# MEGA_Shield.net
KiCad netlist of a schematic drawn in EAGLE
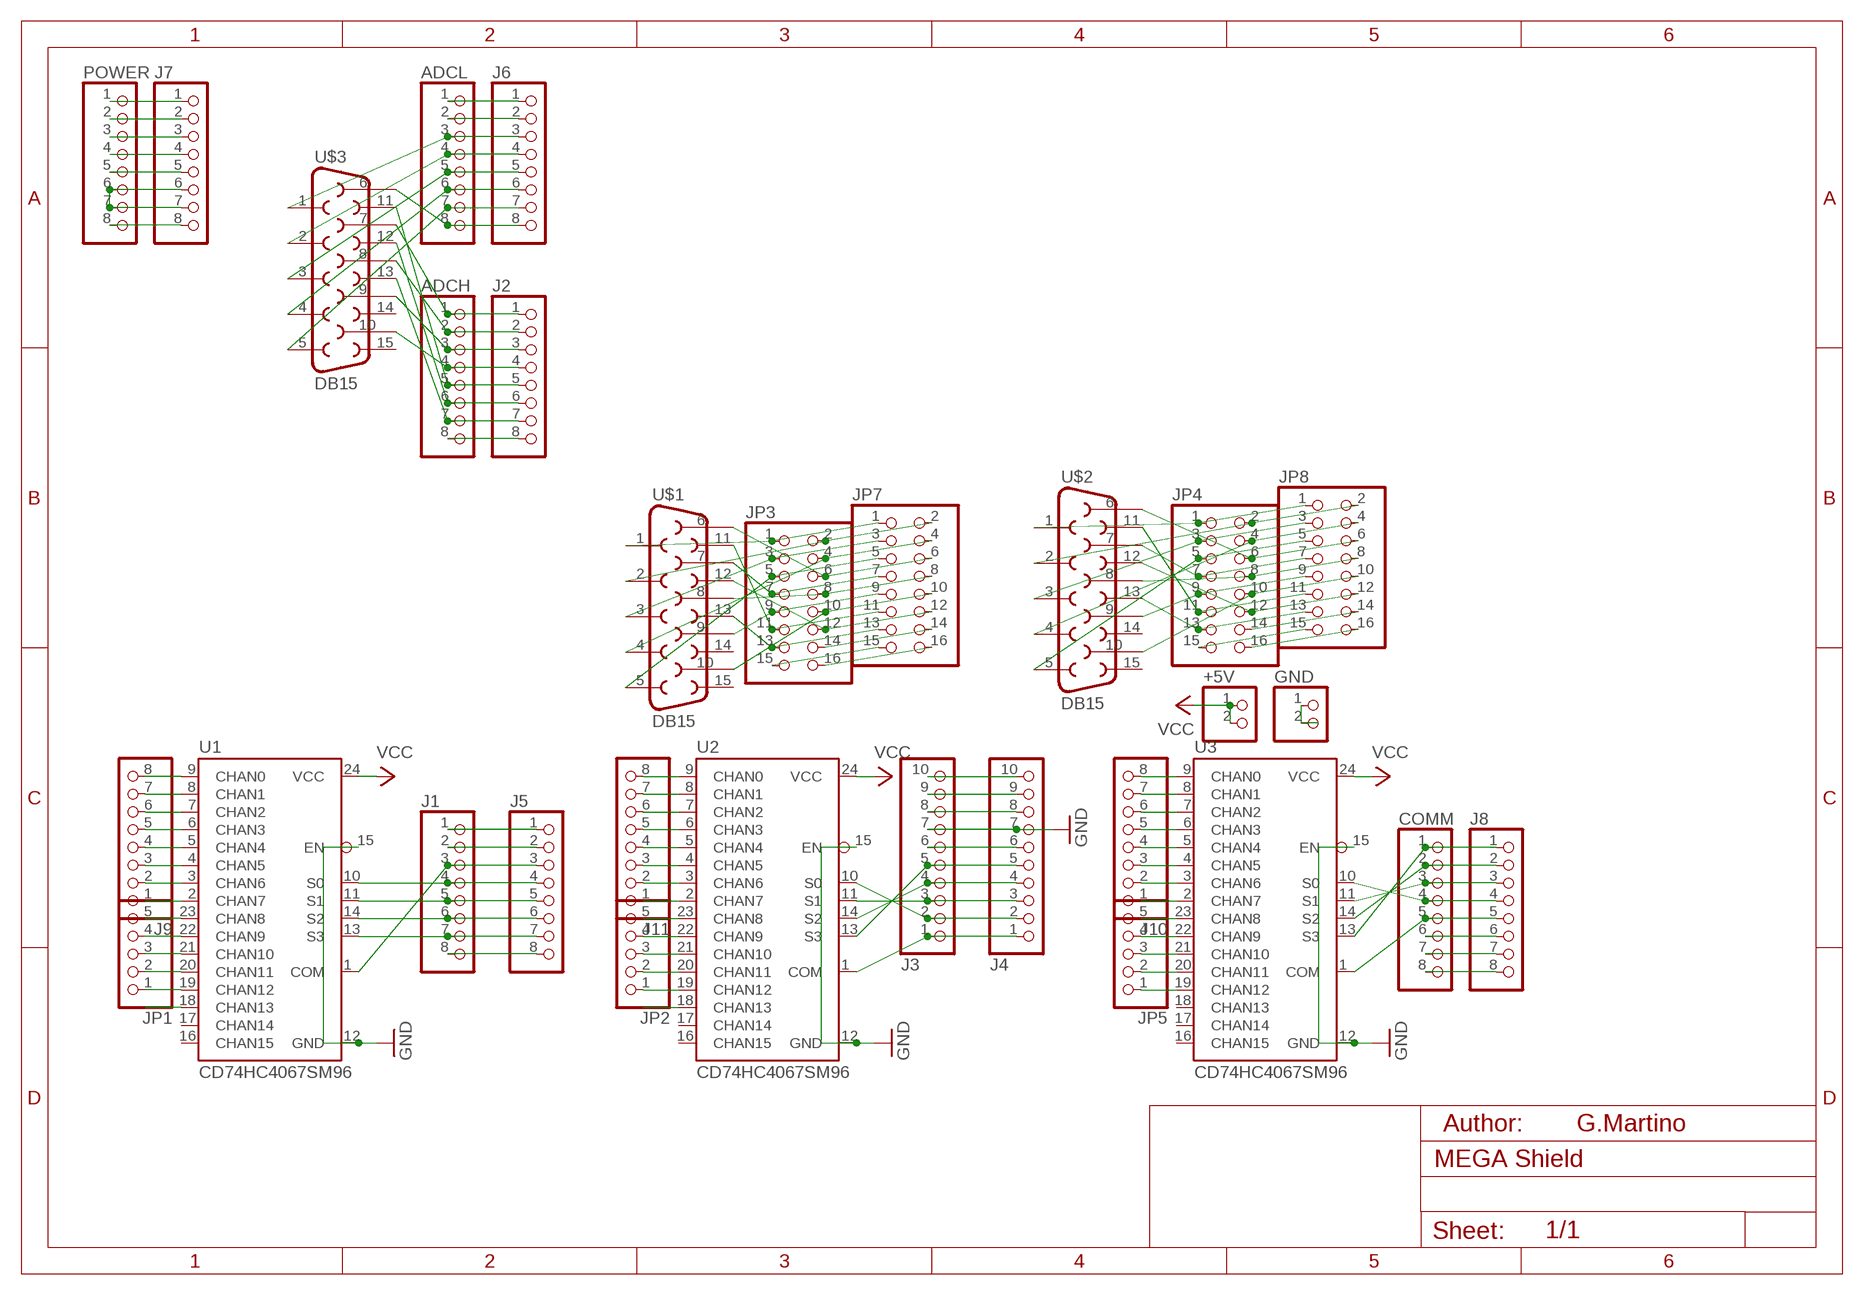
[diagram p0: schematic, sheet 1]

(export (version "E")
  (design (tool "Eeschema 10.0.6"))
  (components
    (comp (ref "+5V")
      (value "PINHD-1X2")
      (footprint "eagle-import:1X02")
      (libsource (lib "eagle-import") (part "PINHD-1X2"))
    )
    (comp (ref "ADCH")
      (value "PINHD-1X8TH")
      (footprint "eagle-import:1X08-TH")
      (libsource (lib "eagle-import") (part "PINHD-1X8TH"))
    )
    (comp (ref "ADCL")
      (value "PINHD-1X8TH")
      (footprint "eagle-import:1X08-TH")
      (libsource (lib "eagle-import") (part "PINHD-1X8TH"))
    )
    (comp (ref "COMM")
      (value "PINHD-1X8TH")
      (footprint "eagle-import:1X08-TH")
      (libsource (lib "eagle-import") (part "PINHD-1X8TH"))
    )
    (comp (ref "GND")
      (value "PINHD-1X2")
      (footprint "eagle-import:1X02")
      (libsource (lib "eagle-import") (part "PINHD-1X2"))
    )
    (comp (ref "J1")
      (value "PINHD-1X8TH")
      (footprint "eagle-import:1X08-TH")
      (libsource (lib "eagle-import") (part "PINHD-1X8TH"))
    )
    (comp (ref "J2")
      (value "PINHD-1X8TH")
      (footprint "eagle-import:1X08-TH")
      (libsource (lib "eagle-import") (part "PINHD-1X8TH"))
    )
    (comp (ref "J3")
      (value "PINHD-1X10TH")
      (footprint "eagle-import:1X10-TH")
      (libsource (lib "eagle-import") (part "PINHD-1X10TH"))
    )
    (comp (ref "J4")
      (value "PINHD-1X10TH")
      (footprint "eagle-import:1X10-TH")
      (libsource (lib "eagle-import") (part "PINHD-1X10TH"))
    )
    (comp (ref "J5")
      (value "PINHD-1X8TH")
      (footprint "eagle-import:1X08-TH")
      (libsource (lib "eagle-import") (part "PINHD-1X8TH"))
    )
    (comp (ref "J6")
      (value "PINHD-1X8TH")
      (footprint "eagle-import:1X08-TH")
      (libsource (lib "eagle-import") (part "PINHD-1X8TH"))
    )
    (comp (ref "J7")
      (value "PINHD-1X8TH")
      (footprint "eagle-import:1X08-TH")
      (libsource (lib "eagle-import") (part "PINHD-1X8TH"))
    )
    (comp (ref "J8")
      (value "PINHD-1X8TH")
      (footprint "eagle-import:1X08-TH")
      (libsource (lib "eagle-import") (part "PINHD-1X8TH"))
    )
    (comp (ref "J9")
      (value "PINHD-1X8TH")
      (footprint "eagle-import:1X08-TH")
      (libsource (lib "eagle-import") (part "PINHD-1X8TH"))
    )
    (comp (ref "J10")
      (value "PINHD-1X8TH")
      (footprint "eagle-import:1X08-TH")
      (libsource (lib "eagle-import") (part "PINHD-1X8TH"))
    )
    (comp (ref "J11")
      (value "PINHD-1X8TH")
      (footprint "eagle-import:1X08-TH")
      (libsource (lib "eagle-import") (part "PINHD-1X8TH"))
    )
    (comp (ref "JP1")
      (value "PINHD-1X5")
      (footprint "eagle-import:1X05")
      (libsource (lib "eagle-import") (part "PINHD-1X5"))
    )
    (comp (ref "JP2")
      (value "PINHD-1X5")
      (footprint "eagle-import:1X05")
      (libsource (lib "eagle-import") (part "PINHD-1X5"))
    )
    (comp (ref "JP3")
      (value "PINHD-2X8")
      (footprint "eagle-import:2X08")
      (libsource (lib "eagle-import") (part "PINHD-2X8"))
    )
    (comp (ref "JP4")
      (value "PINHD-2X8")
      (footprint "eagle-import:2X08")
      (libsource (lib "eagle-import") (part "PINHD-2X8"))
    )
    (comp (ref "JP5")
      (value "PINHD-1X5")
      (footprint "eagle-import:1X05")
      (libsource (lib "eagle-import") (part "PINHD-1X5"))
    )
    (comp (ref "JP7")
      (value "PINHD-2X8")
      (footprint "eagle-import:2X08")
      (libsource (lib "eagle-import") (part "PINHD-2X8"))
    )
    (comp (ref "JP8")
      (value "PINHD-2X8")
      (footprint "eagle-import:2X08")
      (libsource (lib "eagle-import") (part "PINHD-2X8"))
    )
    (comp (ref "POWER")
      (value "PINHD-1X8TH")
      (footprint "eagle-import:1X08-TH")
      (libsource (lib "eagle-import") (part "PINHD-1X8TH"))
    )
    (comp (ref "U$1")
      (value "DB15")
      (footprint "eagle-import:DB15")
      (libsource (lib "eagle-import") (part "DB15"))
    )
    (comp (ref "U$2")
      (value "DB15")
      (footprint "eagle-import:DB15")
      (libsource (lib "eagle-import") (part "DB15"))
    )
    (comp (ref "U$3")
      (value "DB15")
      (footprint "eagle-import:DB15")
      (libsource (lib "eagle-import") (part "DB15"))
    )
    (comp (ref "U1")
      (value "CD74HC4067SM96")
      (footprint "eagle-import:SSOP24")
      (libsource (lib "eagle-import") (part "744067SM96HC"))
    )
    (comp (ref "U2")
      (value "CD74HC4067SM96")
      (footprint "eagle-import:SSOP24")
      (libsource (lib "eagle-import") (part "744067SM96HC"))
    )
    (comp (ref "U3")
      (value "CD74HC4067SM96")
      (footprint "eagle-import:SSOP24")
      (libsource (lib "eagle-import") (part "744067SM96HC"))
    )
  )
  (nets
    (net (code "1") (name "GND") (class "Default")
      (node (ref "J3") (pin "7") (pinfunction "7_7") (pintype "passive"))
      (node (ref "J4") (pin "7") (pinfunction "7_7") (pintype "passive"))
      (node (ref "U1") (pin "12") (pinfunction "GND_12") (pintype "bidirectional"))
      (node (ref "U1") (pin "15") (pinfunction "EN_15") (pintype "input"))
      (node (ref "U2") (pin "12") (pinfunction "GND_12") (pintype "bidirectional"))
      (node (ref "U2") (pin "15") (pinfunction "EN_15") (pintype "input"))
      (node (ref "U3") (pin "12") (pinfunction "GND_12") (pintype "bidirectional"))
      (node (ref "U3") (pin "15") (pinfunction "EN_15") (pintype "input"))
    )
    (net (code "2") (name "Net-(ADCH-Pad1)") (class "Default")
      (node (ref "ADCH") (pin "1") (pinfunction "1_1") (pintype "passive"))
      (node (ref "J2") (pin "1") (pinfunction "1_1") (pintype "passive"))
      (node (ref "U$3") (pin "7") (pinfunction "7_7") (pintype "passive"))
    )
    (net (code "3") (name "Net-(ADCH-Pad2)") (class "Default")
      (node (ref "ADCH") (pin "2") (pinfunction "2_2") (pintype "passive"))
      (node (ref "J2") (pin "2") (pinfunction "2_2") (pintype "passive"))
      (node (ref "U$3") (pin "8") (pinfunction "8_8") (pintype "passive"))
    )
    (net (code "4") (name "Net-(ADCH-Pad3)") (class "Default")
      (node (ref "ADCH") (pin "3") (pinfunction "3_3") (pintype "passive"))
      (node (ref "J2") (pin "3") (pinfunction "3_3") (pintype "passive"))
      (node (ref "U$3") (pin "9") (pinfunction "9_9") (pintype "passive"))
    )
    (net (code "5") (name "Net-(ADCH-Pad4)") (class "Default")
      (node (ref "ADCH") (pin "4") (pinfunction "4_4") (pintype "passive"))
      (node (ref "J2") (pin "4") (pinfunction "4_4") (pintype "passive"))
      (node (ref "U$3") (pin "10") (pinfunction "10_10") (pintype "passive"))
    )
    (net (code "6") (name "Net-(ADCH-Pad5)") (class "Default")
      (node (ref "ADCH") (pin "5") (pinfunction "5_5") (pintype "passive"))
      (node (ref "J2") (pin "5") (pinfunction "5_5") (pintype "passive"))
      (node (ref "U$3") (pin "11") (pinfunction "11_11") (pintype "passive"))
    )
    (net (code "7") (name "Net-(ADCH-Pad6)") (class "Default")
      (node (ref "ADCH") (pin "6") (pinfunction "6_6") (pintype "passive"))
      (node (ref "J2") (pin "6") (pinfunction "6_6") (pintype "passive"))
      (node (ref "U$3") (pin "12") (pinfunction "12_12") (pintype "passive"))
    )
    (net (code "8") (name "Net-(ADCH-Pad7)") (class "Default")
      (node (ref "ADCH") (pin "7") (pinfunction "7_7") (pintype "passive"))
      (node (ref "J2") (pin "7") (pinfunction "7_7") (pintype "passive"))
      (node (ref "U$3") (pin "13") (pinfunction "13_13") (pintype "passive"))
    )
    (net (code "9") (name "Net-(ADCH-Pad8)") (class "Default")
      (node (ref "ADCH") (pin "8") (pinfunction "8_8") (pintype "passive"))
      (node (ref "J2") (pin "8") (pinfunction "8_8") (pintype "passive"))
    )
    (net (code "10") (name "Net-(ADCL-Pad1)") (class "Default")
      (node (ref "ADCL") (pin "1") (pinfunction "1_1") (pintype "passive"))
      (node (ref "J6") (pin "1") (pinfunction "1_1") (pintype "passive"))
    )
    (net (code "11") (name "Net-(ADCL-Pad2)") (class "Default")
      (node (ref "ADCL") (pin "2") (pinfunction "2_2") (pintype "passive"))
      (node (ref "J6") (pin "2") (pinfunction "2_2") (pintype "passive"))
    )
    (net (code "12") (name "Net-(ADCL-Pad3)") (class "Default")
      (node (ref "ADCL") (pin "3") (pinfunction "3_3") (pintype "passive"))
      (node (ref "J6") (pin "3") (pinfunction "3_3") (pintype "passive"))
      (node (ref "U$3") (pin "1") (pinfunction "1_1") (pintype "passive"))
    )
    (net (code "13") (name "Net-(ADCL-Pad4)") (class "Default")
      (node (ref "ADCL") (pin "4") (pinfunction "4_4") (pintype "passive"))
      (node (ref "J6") (pin "4") (pinfunction "4_4") (pintype "passive"))
      (node (ref "U$3") (pin "2") (pinfunction "2_2") (pintype "passive"))
    )
    (net (code "14") (name "Net-(ADCL-Pad5)") (class "Default")
      (node (ref "ADCL") (pin "5") (pinfunction "5_5") (pintype "passive"))
      (node (ref "J6") (pin "5") (pinfunction "5_5") (pintype "passive"))
      (node (ref "U$3") (pin "3") (pinfunction "3_3") (pintype "passive"))
    )
    (net (code "15") (name "Net-(ADCL-Pad6)") (class "Default")
      (node (ref "ADCL") (pin "6") (pinfunction "6_6") (pintype "passive"))
      (node (ref "J6") (pin "6") (pinfunction "6_6") (pintype "passive"))
      (node (ref "U$3") (pin "4") (pinfunction "4_4") (pintype "passive"))
    )
    (net (code "16") (name "Net-(ADCL-Pad7)") (class "Default")
      (node (ref "ADCL") (pin "7") (pinfunction "7_7") (pintype "passive"))
      (node (ref "J6") (pin "7") (pinfunction "7_7") (pintype "passive"))
      (node (ref "U$3") (pin "5") (pinfunction "5_5") (pintype "passive"))
    )
    (net (code "17") (name "Net-(ADCL-Pad8)") (class "Default")
      (node (ref "ADCL") (pin "8") (pinfunction "8_8") (pintype "passive"))
      (node (ref "J6") (pin "8") (pinfunction "8_8") (pintype "passive"))
      (node (ref "U$3") (pin "6") (pinfunction "6_6") (pintype "passive"))
    )
    (net (code "18") (name "Net-(COMM-Pad6)") (class "Default")
      (node (ref "COMM") (pin "6") (pinfunction "6_6") (pintype "passive"))
      (node (ref "J8") (pin "6") (pinfunction "6_6") (pintype "passive"))
    )
    (net (code "19") (name "Net-(COMM-Pad7)") (class "Default")
      (node (ref "COMM") (pin "7") (pinfunction "7_7") (pintype "passive"))
      (node (ref "J8") (pin "7") (pinfunction "7_7") (pintype "passive"))
    )
    (net (code "20") (name "Net-(COMM-Pad8)") (class "Default")
      (node (ref "COMM") (pin "8") (pinfunction "8_8") (pintype "passive"))
      (node (ref "J8") (pin "8") (pinfunction "8_8") (pintype "passive"))
    )
    (net (code "21") (name "Net-(GND-Pad1)") (class "Default")
      (node (ref "GND") (pin "1") (pinfunction "1_1") (pintype "passive"))
      (node (ref "GND") (pin "2") (pinfunction "2_2") (pintype "passive"))
    )
    (net (code "22") (name "Net-(J1-Pad1)") (class "Default")
      (node (ref "J1") (pin "1") (pinfunction "1_1") (pintype "passive"))
      (node (ref "J5") (pin "1") (pinfunction "1_1") (pintype "passive"))
    )
    (net (code "23") (name "Net-(J1-Pad2)") (class "Default")
      (node (ref "J1") (pin "2") (pinfunction "2_2") (pintype "passive"))
      (node (ref "J5") (pin "2") (pinfunction "2_2") (pintype "passive"))
    )
    (net (code "24") (name "Net-(J1-Pad8)") (class "Default")
      (node (ref "J1") (pin "8") (pinfunction "8_8") (pintype "passive"))
      (node (ref "J5") (pin "8") (pinfunction "8_8") (pintype "passive"))
    )
    (net (code "25") (name "Net-(J3-Pad6)") (class "Default")
      (node (ref "J3") (pin "6") (pinfunction "6_6") (pintype "passive"))
      (node (ref "J4") (pin "6") (pinfunction "6_6") (pintype "passive"))
    )
    (net (code "26") (name "Net-(J3-Pad8)") (class "Default")
      (node (ref "J3") (pin "8") (pinfunction "8_8") (pintype "passive"))
      (node (ref "J4") (pin "8") (pinfunction "8_8") (pintype "passive"))
    )
    (net (code "27") (name "Net-(J3-Pad9)") (class "Default")
      (node (ref "J3") (pin "9") (pinfunction "9_9") (pintype "passive"))
      (node (ref "J4") (pin "9") (pinfunction "9_9") (pintype "passive"))
    )
    (net (code "28") (name "Net-(J3-Pad10)") (class "Default")
      (node (ref "J3") (pin "10") (pinfunction "10_10") (pintype "passive"))
      (node (ref "J4") (pin "10") (pinfunction "10_10") (pintype "passive"))
    )
    (net (code "29") (name "Net-(J7-Pad1)") (class "Default")
      (node (ref "J7") (pin "1") (pinfunction "1_1") (pintype "passive"))
      (node (ref "POWER") (pin "1") (pinfunction "1_1") (pintype "passive"))
    )
    (net (code "30") (name "Net-(J7-Pad2)") (class "Default")
      (node (ref "J7") (pin "2") (pinfunction "2_2") (pintype "passive"))
      (node (ref "POWER") (pin "2") (pinfunction "2_2") (pintype "passive"))
    )
    (net (code "31") (name "Net-(J7-Pad3)") (class "Default")
      (node (ref "J7") (pin "3") (pinfunction "3_3") (pintype "passive"))
      (node (ref "POWER") (pin "3") (pinfunction "3_3") (pintype "passive"))
    )
    (net (code "32") (name "Net-(J7-Pad4)") (class "Default")
      (node (ref "J7") (pin "4") (pinfunction "4_4") (pintype "passive"))
      (node (ref "POWER") (pin "4") (pinfunction "4_4") (pintype "passive"))
    )
    (net (code "33") (name "Net-(J7-Pad5)") (class "Default")
      (node (ref "J7") (pin "5") (pinfunction "5_5") (pintype "passive"))
      (node (ref "POWER") (pin "5") (pinfunction "5_5") (pintype "passive"))
    )
    (net (code "34") (name "Net-(J7-Pad6)") (class "Default")
      (node (ref "J7") (pin "6") (pinfunction "6_6") (pintype "passive"))
      (node (ref "J7") (pin "7") (pinfunction "7_7") (pintype "passive"))
      (node (ref "POWER") (pin "6") (pinfunction "6_6") (pintype "passive"))
      (node (ref "POWER") (pin "7") (pinfunction "7_7") (pintype "passive"))
    )
    (net (code "35") (name "Net-(J7-Pad8)") (class "Default")
      (node (ref "J7") (pin "8") (pinfunction "8_8") (pintype "passive"))
      (node (ref "POWER") (pin "8") (pinfunction "8_8") (pintype "passive"))
    )
    (net (code "36") (name "Net-(JP3-Pad1)") (class "Default")
      (node (ref "JP3") (pin "1") (pinfunction "1_1") (pintype "passive"))
      (node (ref "JP7") (pin "1") (pinfunction "1_1") (pintype "passive"))
      (node (ref "U$1") (pin "1") (pinfunction "1_1") (pintype "passive"))
    )
    (net (code "37") (name "Net-(JP3-Pad2)") (class "Default")
      (node (ref "JP3") (pin "2") (pinfunction "2_2") (pintype "passive"))
      (node (ref "JP7") (pin "2") (pinfunction "2_2") (pintype "passive"))
      (node (ref "U$1") (pin "2") (pinfunction "2_2") (pintype "passive"))
    )
    (net (code "38") (name "Net-(JP3-Pad3)") (class "Default")
      (node (ref "JP3") (pin "3") (pinfunction "3_3") (pintype "passive"))
      (node (ref "JP7") (pin "3") (pinfunction "3_3") (pintype "passive"))
      (node (ref "U$1") (pin "3") (pinfunction "3_3") (pintype "passive"))
    )
    (net (code "39") (name "Net-(JP3-Pad4)") (class "Default")
      (node (ref "JP3") (pin "4") (pinfunction "4_4") (pintype "passive"))
      (node (ref "JP7") (pin "4") (pinfunction "4_4") (pintype "passive"))
      (node (ref "U$1") (pin "4") (pinfunction "4_4") (pintype "passive"))
    )
    (net (code "40") (name "Net-(JP3-Pad5)") (class "Default")
      (node (ref "JP3") (pin "5") (pinfunction "5_5") (pintype "passive"))
      (node (ref "JP7") (pin "5") (pinfunction "5_5") (pintype "passive"))
      (node (ref "U$1") (pin "5") (pinfunction "5_5") (pintype "passive"))
    )
    (net (code "41") (name "Net-(JP3-Pad6)") (class "Default")
      (node (ref "JP3") (pin "6") (pinfunction "6_6") (pintype "passive"))
      (node (ref "JP7") (pin "6") (pinfunction "6_6") (pintype "passive"))
      (node (ref "U$1") (pin "6") (pinfunction "6_6") (pintype "passive"))
    )
    (net (code "42") (name "Net-(JP3-Pad7)") (class "Default")
      (node (ref "JP3") (pin "7") (pinfunction "7_7") (pintype "passive"))
      (node (ref "JP7") (pin "7") (pinfunction "7_7") (pintype "passive"))
      (node (ref "U$1") (pin "7") (pinfunction "7_7") (pintype "passive"))
    )
    (net (code "43") (name "Net-(JP3-Pad8)") (class "Default")
      (node (ref "JP3") (pin "8") (pinfunction "8_8") (pintype "passive"))
      (node (ref "JP7") (pin "8") (pinfunction "8_8") (pintype "passive"))
      (node (ref "U$1") (pin "8") (pinfunction "8_8") (pintype "passive"))
    )
    (net (code "44") (name "Net-(JP3-Pad9)") (class "Default")
      (node (ref "JP3") (pin "9") (pinfunction "9_9") (pintype "passive"))
      (node (ref "JP7") (pin "9") (pinfunction "9_9") (pintype "passive"))
      (node (ref "U$1") (pin "9") (pinfunction "9_9") (pintype "passive"))
    )
    (net (code "45") (name "Net-(JP3-Pad10)") (class "Default")
      (node (ref "JP3") (pin "10") (pinfunction "10_10") (pintype "passive"))
      (node (ref "JP7") (pin "10") (pinfunction "10_10") (pintype "passive"))
      (node (ref "U$1") (pin "10") (pinfunction "10_10") (pintype "passive"))
    )
    (net (code "46") (name "Net-(JP3-Pad11)") (class "Default")
      (node (ref "JP3") (pin "11") (pinfunction "11_11") (pintype "passive"))
      (node (ref "JP7") (pin "11") (pinfunction "11_11") (pintype "passive"))
      (node (ref "U$1") (pin "11") (pinfunction "11_11") (pintype "passive"))
    )
    (net (code "47") (name "Net-(JP3-Pad12)") (class "Default")
      (node (ref "JP3") (pin "12") (pinfunction "12_12") (pintype "passive"))
      (node (ref "JP7") (pin "12") (pinfunction "12_12") (pintype "passive"))
      (node (ref "U$1") (pin "12") (pinfunction "12_12") (pintype "passive"))
    )
    (net (code "48") (name "Net-(JP3-Pad13)") (class "Default")
      (node (ref "JP3") (pin "13") (pinfunction "13_13") (pintype "passive"))
      (node (ref "JP7") (pin "13") (pinfunction "13_13") (pintype "passive"))
      (node (ref "U$1") (pin "13") (pinfunction "13_13") (pintype "passive"))
    )
    (net (code "49") (name "Net-(JP3-Pad14)") (class "Default")
      (node (ref "JP3") (pin "14") (pinfunction "14_14") (pintype "passive"))
      (node (ref "JP7") (pin "14") (pinfunction "14_14") (pintype "passive"))
    )
    (net (code "50") (name "Net-(JP3-Pad15)") (class "Default")
      (node (ref "JP3") (pin "15") (pinfunction "15_15") (pintype "passive"))
      (node (ref "JP7") (pin "15") (pinfunction "15_15") (pintype "passive"))
    )
    (net (code "51") (name "Net-(JP3-Pad16)") (class "Default")
      (node (ref "JP3") (pin "16") (pinfunction "16_16") (pintype "passive"))
      (node (ref "JP7") (pin "16") (pinfunction "16_16") (pintype "passive"))
    )
    (net (code "52") (name "Net-(JP4-Pad1)") (class "Default")
      (node (ref "JP4") (pin "1") (pinfunction "1_1") (pintype "passive"))
      (node (ref "JP8") (pin "1") (pinfunction "1_1") (pintype "passive"))
      (node (ref "U$2") (pin "1") (pinfunction "1_1") (pintype "passive"))
    )
    (net (code "53") (name "Net-(JP4-Pad2)") (class "Default")
      (node (ref "JP4") (pin "2") (pinfunction "2_2") (pintype "passive"))
      (node (ref "JP8") (pin "2") (pinfunction "2_2") (pintype "passive"))
      (node (ref "U$2") (pin "2") (pinfunction "2_2") (pintype "passive"))
    )
    (net (code "54") (name "Net-(JP4-Pad3)") (class "Default")
      (node (ref "JP4") (pin "3") (pinfunction "3_3") (pintype "passive"))
      (node (ref "JP8") (pin "3") (pinfunction "3_3") (pintype "passive"))
      (node (ref "U$2") (pin "3") (pinfunction "3_3") (pintype "passive"))
    )
    (net (code "55") (name "Net-(JP4-Pad4)") (class "Default")
      (node (ref "JP4") (pin "4") (pinfunction "4_4") (pintype "passive"))
      (node (ref "JP8") (pin "4") (pinfunction "4_4") (pintype "passive"))
      (node (ref "U$2") (pin "4") (pinfunction "4_4") (pintype "passive"))
    )
    (net (code "56") (name "Net-(JP4-Pad5)") (class "Default")
      (node (ref "JP4") (pin "5") (pinfunction "5_5") (pintype "passive"))
      (node (ref "JP8") (pin "5") (pinfunction "5_5") (pintype "passive"))
      (node (ref "U$2") (pin "5") (pinfunction "5_5") (pintype "passive"))
    )
    (net (code "57") (name "Net-(JP4-Pad6)") (class "Default")
      (node (ref "JP4") (pin "6") (pinfunction "6_6") (pintype "passive"))
      (node (ref "JP8") (pin "6") (pinfunction "6_6") (pintype "passive"))
      (node (ref "U$2") (pin "6") (pinfunction "6_6") (pintype "passive"))
    )
    (net (code "58") (name "Net-(JP4-Pad7)") (class "Default")
      (node (ref "JP4") (pin "7") (pinfunction "7_7") (pintype "passive"))
      (node (ref "JP8") (pin "7") (pinfunction "7_7") (pintype "passive"))
      (node (ref "U$2") (pin "7") (pinfunction "7_7") (pintype "passive"))
    )
    (net (code "59") (name "Net-(JP4-Pad8)") (class "Default")
      (node (ref "JP4") (pin "8") (pinfunction "8_8") (pintype "passive"))
      (node (ref "JP8") (pin "8") (pinfunction "8_8") (pintype "passive"))
      (node (ref "U$2") (pin "8") (pinfunction "8_8") (pintype "passive"))
    )
    (net (code "60") (name "Net-(JP4-Pad9)") (class "Default")
      (node (ref "JP4") (pin "9") (pinfunction "9_9") (pintype "passive"))
      (node (ref "JP8") (pin "9") (pinfunction "9_9") (pintype "passive"))
      (node (ref "U$2") (pin "9") (pinfunction "9_9") (pintype "passive"))
    )
    (net (code "61") (name "Net-(JP4-Pad10)") (class "Default")
      (node (ref "JP4") (pin "10") (pinfunction "10_10") (pintype "passive"))
      (node (ref "JP8") (pin "10") (pinfunction "10_10") (pintype "passive"))
      (node (ref "U$2") (pin "10") (pinfunction "10_10") (pintype "passive"))
    )
    (net (code "62") (name "Net-(JP4-Pad11)") (class "Default")
      (node (ref "JP4") (pin "11") (pinfunction "11_11") (pintype "passive"))
      (node (ref "JP8") (pin "11") (pinfunction "11_11") (pintype "passive"))
      (node (ref "U$2") (pin "11") (pinfunction "11_11") (pintype "passive"))
    )
    (net (code "63") (name "Net-(JP4-Pad12)") (class "Default")
      (node (ref "JP4") (pin "12") (pinfunction "12_12") (pintype "passive"))
      (node (ref "JP8") (pin "12") (pinfunction "12_12") (pintype "passive"))
      (node (ref "U$2") (pin "12") (pinfunction "12_12") (pintype "passive"))
    )
    (net (code "64") (name "Net-(JP4-Pad13)") (class "Default")
      (node (ref "JP4") (pin "13") (pinfunction "13_13") (pintype "passive"))
      (node (ref "JP8") (pin "13") (pinfunction "13_13") (pintype "passive"))
      (node (ref "U$2") (pin "13") (pinfunction "13_13") (pintype "passive"))
    )
    (net (code "65") (name "Net-(JP4-Pad14)") (class "Default")
      (node (ref "JP4") (pin "14") (pinfunction "14_14") (pintype "passive"))
      (node (ref "JP8") (pin "14") (pinfunction "14_14") (pintype "passive"))
    )
    (net (code "66") (name "Net-(JP4-Pad15)") (class "Default")
      (node (ref "JP4") (pin "15") (pinfunction "15_15") (pintype "passive"))
      (node (ref "JP8") (pin "15") (pinfunction "15_15") (pintype "passive"))
    )
    (net (code "67") (name "Net-(JP4-Pad16)") (class "Default")
      (node (ref "JP4") (pin "16") (pinfunction "16_16") (pintype "passive"))
      (node (ref "JP8") (pin "16") (pinfunction "16_16") (pintype "passive"))
    )
    (net (code "68") (name "Net-(U1-CHAN0)") (class "Default")
      (node (ref "J9") (pin "8") (pinfunction "8_8") (pintype "passive"))
      (node (ref "U1") (pin "9") (pinfunction "CHAN0_9") (pintype "bidirectional"))
    )
    (net (code "69") (name "Net-(U1-CHAN1)") (class "Default")
      (node (ref "J9") (pin "7") (pinfunction "7_7") (pintype "passive"))
      (node (ref "U1") (pin "8") (pinfunction "CHAN1_8") (pintype "bidirectional"))
    )
    (net (code "70") (name "Net-(U1-CHAN2)") (class "Default")
      (node (ref "J9") (pin "6") (pinfunction "6_6") (pintype "passive"))
      (node (ref "U1") (pin "7") (pinfunction "CHAN2_7") (pintype "bidirectional"))
    )
    (net (code "71") (name "Net-(U1-CHAN3)") (class "Default")
      (node (ref "J9") (pin "5") (pinfunction "5_5") (pintype "passive"))
      (node (ref "U1") (pin "6") (pinfunction "CHAN3_6") (pintype "bidirectional"))
    )
    (net (code "72") (name "Net-(U1-CHAN4)") (class "Default")
      (node (ref "J9") (pin "4") (pinfunction "4_4") (pintype "passive"))
      (node (ref "U1") (pin "5") (pinfunction "CHAN4_5") (pintype "bidirectional"))
    )
    (net (code "73") (name "Net-(U1-CHAN5)") (class "Default")
      (node (ref "J9") (pin "3") (pinfunction "3_3") (pintype "passive"))
      (node (ref "U1") (pin "4") (pinfunction "CHAN5_4") (pintype "bidirectional"))
    )
    (net (code "74") (name "Net-(U1-CHAN6)") (class "Default")
      (node (ref "J9") (pin "2") (pinfunction "2_2") (pintype "passive"))
      (node (ref "U1") (pin "3") (pinfunction "CHAN6_3") (pintype "bidirectional"))
    )
    (net (code "75") (name "Net-(U1-CHAN7)") (class "Default")
      (node (ref "J9") (pin "1") (pinfunction "1_1") (pintype "passive"))
      (node (ref "U1") (pin "2") (pinfunction "CHAN7_2") (pintype "bidirectional"))
    )
    (net (code "76") (name "Net-(U1-CHAN8)") (class "Default")
      (node (ref "JP1") (pin "5") (pinfunction "5_5") (pintype "passive"))
      (node (ref "U1") (pin "23") (pinfunction "CHAN8_23") (pintype "bidirectional"))
    )
    (net (code "77") (name "Net-(U1-CHAN9)") (class "Default")
      (node (ref "JP1") (pin "4") (pinfunction "4_4") (pintype "passive"))
      (node (ref "U1") (pin "22") (pinfunction "CHAN9_22") (pintype "bidirectional"))
    )
    (net (code "78") (name "Net-(U1-CHAN10)") (class "Default")
      (node (ref "JP1") (pin "3") (pinfunction "3_3") (pintype "passive"))
      (node (ref "U1") (pin "21") (pinfunction "CHAN10_21") (pintype "bidirectional"))
    )
    (net (code "79") (name "Net-(U1-CHAN11)") (class "Default")
      (node (ref "JP1") (pin "2") (pinfunction "2_2") (pintype "passive"))
      (node (ref "U1") (pin "20") (pinfunction "CHAN11_20") (pintype "bidirectional"))
    )
    (net (code "80") (name "Net-(U1-CHAN12)") (class "Default")
      (node (ref "JP1") (pin "1") (pinfunction "1_1") (pintype "passive"))
      (node (ref "U1") (pin "19") (pinfunction "CHAN12_19") (pintype "bidirectional"))
    )
    (net (code "81") (name "Net-(U1-COM)") (class "Default")
      (node (ref "J1") (pin "3") (pinfunction "3_3") (pintype "passive"))
      (node (ref "J5") (pin "3") (pinfunction "3_3") (pintype "passive"))
      (node (ref "U1") (pin "1") (pinfunction "COM_1") (pintype "bidirectional"))
    )
    (net (code "82") (name "Net-(U1-S0)") (class "Default")
      (node (ref "J1") (pin "4") (pinfunction "4_4") (pintype "passive"))
      (node (ref "J5") (pin "4") (pinfunction "4_4") (pintype "passive"))
      (node (ref "U1") (pin "10") (pinfunction "S0_10") (pintype "input"))
    )
    (net (code "83") (name "Net-(U1-S1)") (class "Default")
      (node (ref "J1") (pin "5") (pinfunction "5_5") (pintype "passive"))
      (node (ref "J5") (pin "5") (pinfunction "5_5") (pintype "passive"))
      (node (ref "U1") (pin "11") (pinfunction "S1_11") (pintype "input"))
    )
    (net (code "84") (name "Net-(U1-S2)") (class "Default")
      (node (ref "J1") (pin "6") (pinfunction "6_6") (pintype "passive"))
      (node (ref "J5") (pin "6") (pinfunction "6_6") (pintype "passive"))
      (node (ref "U1") (pin "14") (pinfunction "S2_14") (pintype "input"))
    )
    (net (code "85") (name "Net-(U1-S3)") (class "Default")
      (node (ref "J1") (pin "7") (pinfunction "7_7") (pintype "passive"))
      (node (ref "J5") (pin "7") (pinfunction "7_7") (pintype "passive"))
      (node (ref "U1") (pin "13") (pinfunction "S3_13") (pintype "input"))
    )
    (net (code "86") (name "Net-(U2-CHAN0)") (class "Default")
      (node (ref "J11") (pin "8") (pinfunction "8_8") (pintype "passive"))
      (node (ref "U2") (pin "9") (pinfunction "CHAN0_9") (pintype "bidirectional"))
    )
    (net (code "87") (name "Net-(U2-CHAN1)") (class "Default")
      (node (ref "J11") (pin "7") (pinfunction "7_7") (pintype "passive"))
      (node (ref "U2") (pin "8") (pinfunction "CHAN1_8") (pintype "bidirectional"))
    )
    (net (code "88") (name "Net-(U2-CHAN2)") (class "Default")
      (node (ref "J11") (pin "6") (pinfunction "6_6") (pintype "passive"))
      (node (ref "U2") (pin "7") (pinfunction "CHAN2_7") (pintype "bidirectional"))
    )
    (net (code "89") (name "Net-(U2-CHAN3)") (class "Default")
      (node (ref "J11") (pin "5") (pinfunction "5_5") (pintype "passive"))
      (node (ref "U2") (pin "6") (pinfunction "CHAN3_6") (pintype "bidirectional"))
    )
    (net (code "90") (name "Net-(U2-CHAN4)") (class "Default")
      (node (ref "J11") (pin "4") (pinfunction "4_4") (pintype "passive"))
      (node (ref "U2") (pin "5") (pinfunction "CHAN4_5") (pintype "bidirectional"))
    )
    (net (code "91") (name "Net-(U2-CHAN5)") (class "Default")
      (node (ref "J11") (pin "3") (pinfunction "3_3") (pintype "passive"))
      (node (ref "U2") (pin "4") (pinfunction "CHAN5_4") (pintype "bidirectional"))
    )
    (net (code "92") (name "Net-(U2-CHAN6)") (class "Default")
      (node (ref "J11") (pin "2") (pinfunction "2_2") (pintype "passive"))
      (node (ref "U2") (pin "3") (pinfunction "CHAN6_3") (pintype "bidirectional"))
    )
    (net (code "93") (name "Net-(U2-CHAN7)") (class "Default")
      (node (ref "J11") (pin "1") (pinfunction "1_1") (pintype "passive"))
      (node (ref "U2") (pin "2") (pinfunction "CHAN7_2") (pintype "bidirectional"))
    )
    (net (code "94") (name "Net-(U2-CHAN8)") (class "Default")
      (node (ref "JP2") (pin "5") (pinfunction "5_5") (pintype "passive"))
      (node (ref "U2") (pin "23") (pinfunction "CHAN8_23") (pintype "bidirectional"))
    )
    (net (code "95") (name "Net-(U2-CHAN9)") (class "Default")
      (node (ref "JP2") (pin "4") (pinfunction "4_4") (pintype "passive"))
      (node (ref "U2") (pin "22") (pinfunction "CHAN9_22") (pintype "bidirectional"))
    )
    (net (code "96") (name "Net-(U2-CHAN10)") (class "Default")
      (node (ref "JP2") (pin "3") (pinfunction "3_3") (pintype "passive"))
      (node (ref "U2") (pin "21") (pinfunction "CHAN10_21") (pintype "bidirectional"))
    )
    (net (code "97") (name "Net-(U2-CHAN11)") (class "Default")
      (node (ref "JP2") (pin "2") (pinfunction "2_2") (pintype "passive"))
      (node (ref "U2") (pin "20") (pinfunction "CHAN11_20") (pintype "bidirectional"))
    )
    (net (code "98") (name "Net-(U2-CHAN12)") (class "Default")
      (node (ref "JP2") (pin "1") (pinfunction "1_1") (pintype "passive"))
      (node (ref "U2") (pin "19") (pinfunction "CHAN12_19") (pintype "bidirectional"))
    )
    (net (code "99") (name "Net-(U2-COM)") (class "Default")
      (node (ref "J3") (pin "1") (pinfunction "1_1") (pintype "passive"))
      (node (ref "J4") (pin "1") (pinfunction "1_1") (pintype "passive"))
      (node (ref "U2") (pin "1") (pinfunction "COM_1") (pintype "bidirectional"))
    )
    (net (code "100") (name "Net-(U2-S0)") (class "Default")
      (node (ref "J3") (pin "2") (pinfunction "2_2") (pintype "passive"))
      (node (ref "J4") (pin "2") (pinfunction "2_2") (pintype "passive"))
      (node (ref "U2") (pin "10") (pinfunction "S0_10") (pintype "input"))
    )
    (net (code "101") (name "Net-(U2-S1)") (class "Default")
      (node (ref "J3") (pin "3") (pinfunction "3_3") (pintype "passive"))
      (node (ref "J4") (pin "3") (pinfunction "3_3") (pintype "passive"))
      (node (ref "U2") (pin "11") (pinfunction "S1_11") (pintype "input"))
    )
    (net (code "102") (name "Net-(U2-S2)") (class "Default")
      (node (ref "J3") (pin "4") (pinfunction "4_4") (pintype "passive"))
      (node (ref "J4") (pin "4") (pinfunction "4_4") (pintype "passive"))
      (node (ref "U2") (pin "14") (pinfunction "S2_14") (pintype "input"))
    )
    (net (code "103") (name "Net-(U2-S3)") (class "Default")
      (node (ref "J3") (pin "5") (pinfunction "5_5") (pintype "passive"))
      (node (ref "J4") (pin "5") (pinfunction "5_5") (pintype "passive"))
      (node (ref "U2") (pin "13") (pinfunction "S3_13") (pintype "input"))
    )
    (net (code "104") (name "Net-(U3-CHAN0)") (class "Default")
      (node (ref "J10") (pin "8") (pinfunction "8_8") (pintype "passive"))
      (node (ref "U3") (pin "9") (pinfunction "CHAN0_9") (pintype "bidirectional"))
    )
    (net (code "105") (name "Net-(U3-CHAN1)") (class "Default")
      (node (ref "J10") (pin "7") (pinfunction "7_7") (pintype "passive"))
      (node (ref "U3") (pin "8") (pinfunction "CHAN1_8") (pintype "bidirectional"))
    )
    (net (code "106") (name "Net-(U3-CHAN2)") (class "Default")
      (node (ref "J10") (pin "6") (pinfunction "6_6") (pintype "passive"))
      (node (ref "U3") (pin "7") (pinfunction "CHAN2_7") (pintype "bidirectional"))
    )
    (net (code "107") (name "Net-(U3-CHAN3)") (class "Default")
      (node (ref "J10") (pin "5") (pinfunction "5_5") (pintype "passive"))
      (node (ref "U3") (pin "6") (pinfunction "CHAN3_6") (pintype "bidirectional"))
    )
    (net (code "108") (name "Net-(U3-CHAN4)") (class "Default")
      (node (ref "J10") (pin "4") (pinfunction "4_4") (pintype "passive"))
      (node (ref "U3") (pin "5") (pinfunction "CHAN4_5") (pintype "bidirectional"))
    )
    (net (code "109") (name "Net-(U3-CHAN5)") (class "Default")
      (node (ref "J10") (pin "3") (pinfunction "3_3") (pintype "passive"))
      (node (ref "U3") (pin "4") (pinfunction "CHAN5_4") (pintype "bidirectional"))
    )
    (net (code "110") (name "Net-(U3-CHAN6)") (class "Default")
      (node (ref "J10") (pin "2") (pinfunction "2_2") (pintype "passive"))
      (node (ref "U3") (pin "3") (pinfunction "CHAN6_3") (pintype "bidirectional"))
    )
    (net (code "111") (name "Net-(U3-CHAN7)") (class "Default")
      (node (ref "J10") (pin "1") (pinfunction "1_1") (pintype "passive"))
      (node (ref "U3") (pin "2") (pinfunction "CHAN7_2") (pintype "bidirectional"))
    )
    (net (code "112") (name "Net-(U3-CHAN8)") (class "Default")
      (node (ref "JP5") (pin "5") (pinfunction "5_5") (pintype "passive"))
      (node (ref "U3") (pin "23") (pinfunction "CHAN8_23") (pintype "bidirectional"))
    )
    (net (code "113") (name "Net-(U3-CHAN9)") (class "Default")
      (node (ref "JP5") (pin "4") (pinfunction "4_4") (pintype "passive"))
      (node (ref "U3") (pin "22") (pinfunction "CHAN9_22") (pintype "bidirectional"))
    )
    (net (code "114") (name "Net-(U3-CHAN10)") (class "Default")
      (node (ref "JP5") (pin "3") (pinfunction "3_3") (pintype "passive"))
      (node (ref "U3") (pin "21") (pinfunction "CHAN10_21") (pintype "bidirectional"))
    )
    (net (code "115") (name "Net-(U3-CHAN11)") (class "Default")
      (node (ref "JP5") (pin "2") (pinfunction "2_2") (pintype "passive"))
      (node (ref "U3") (pin "20") (pinfunction "CHAN11_20") (pintype "bidirectional"))
    )
    (net (code "116") (name "Net-(U3-CHAN12)") (class "Default")
      (node (ref "JP5") (pin "1") (pinfunction "1_1") (pintype "passive"))
      (node (ref "U3") (pin "19") (pinfunction "CHAN12_19") (pintype "bidirectional"))
    )
    (net (code "117") (name "Net-(U3-COM)") (class "Default")
      (node (ref "COMM") (pin "5") (pinfunction "5_5") (pintype "passive"))
      (node (ref "J8") (pin "5") (pinfunction "5_5") (pintype "passive"))
      (node (ref "U3") (pin "1") (pinfunction "COM_1") (pintype "bidirectional"))
    )
    (net (code "118") (name "Net-(U3-S0)") (class "Default")
      (node (ref "COMM") (pin "4") (pinfunction "4_4") (pintype "passive"))
      (node (ref "J8") (pin "4") (pinfunction "4_4") (pintype "passive"))
      (node (ref "U3") (pin "10") (pinfunction "S0_10") (pintype "input"))
    )
    (net (code "119") (name "Net-(U3-S1)") (class "Default")
      (node (ref "COMM") (pin "3") (pinfunction "3_3") (pintype "passive"))
      (node (ref "J8") (pin "3") (pinfunction "3_3") (pintype "passive"))
      (node (ref "U3") (pin "11") (pinfunction "S1_11") (pintype "input"))
    )
    (net (code "120") (name "Net-(U3-S2)") (class "Default")
      (node (ref "COMM") (pin "2") (pinfunction "2_2") (pintype "passive"))
      (node (ref "J8") (pin "2") (pinfunction "2_2") (pintype "passive"))
      (node (ref "U3") (pin "14") (pinfunction "S2_14") (pintype "input"))
    )
    (net (code "121") (name "Net-(U3-S3)") (class "Default")
      (node (ref "COMM") (pin "1") (pinfunction "1_1") (pintype "passive"))
      (node (ref "J8") (pin "1") (pinfunction "1_1") (pintype "passive"))
      (node (ref "U3") (pin "13") (pinfunction "S3_13") (pintype "input"))
    )
    (net (code "122") (name "VCC") (class "Default")
      (node (ref "+5V") (pin "1") (pinfunction "1_1") (pintype "passive"))
      (node (ref "+5V") (pin "2") (pinfunction "2_2") (pintype "passive"))
      (node (ref "U1") (pin "24") (pinfunction "VCC_24") (pintype "bidirectional"))
      (node (ref "U2") (pin "24") (pinfunction "VCC_24") (pintype "bidirectional"))
      (node (ref "U3") (pin "24") (pinfunction "VCC_24") (pintype "bidirectional"))
    )
    (net (code "123") (name "unconnected-(U$1-Pad14)") (class "Default")
      (node (ref "U$1") (pin "14") (pinfunction "14_14") (pintype "passive"))
    )
    (net (code "124") (name "unconnected-(U$1-Pad15)") (class "Default")
      (node (ref "U$1") (pin "15") (pinfunction "15_15") (pintype "passive"))
    )
    (net (code "125") (name "unconnected-(U$2-Pad14)") (class "Default")
      (node (ref "U$2") (pin "14") (pinfunction "14_14") (pintype "passive"))
    )
    (net (code "126") (name "unconnected-(U$2-Pad15)") (class "Default")
      (node (ref "U$2") (pin "15") (pinfunction "15_15") (pintype "passive"))
    )
    (net (code "127") (name "unconnected-(U$3-Pad14)") (class "Default")
      (node (ref "U$3") (pin "14") (pinfunction "14_14") (pintype "passive"))
    )
    (net (code "128") (name "unconnected-(U$3-Pad15)") (class "Default")
      (node (ref "U$3") (pin "15") (pinfunction "15_15") (pintype "passive"))
    )
    (net (code "129") (name "unconnected-(U1-CHAN13-Pad18)") (class "Default")
      (node (ref "U1") (pin "18") (pinfunction "CHAN13_18") (pintype "bidirectional"))
    )
    (net (code "130") (name "unconnected-(U1-CHAN14-Pad17)") (class "Default")
      (node (ref "U1") (pin "17") (pinfunction "CHAN14_17") (pintype "bidirectional"))
    )
    (net (code "131") (name "unconnected-(U1-CHAN15-Pad16)") (class "Default")
      (node (ref "U1") (pin "16") (pinfunction "CHAN15_16") (pintype "bidirectional"))
    )
    (net (code "132") (name "unconnected-(U2-CHAN13-Pad18)") (class "Default")
      (node (ref "U2") (pin "18") (pinfunction "CHAN13_18") (pintype "bidirectional"))
    )
    (net (code "133") (name "unconnected-(U2-CHAN14-Pad17)") (class "Default")
      (node (ref "U2") (pin "17") (pinfunction "CHAN14_17") (pintype "bidirectional"))
    )
    (net (code "134") (name "unconnected-(U2-CHAN15-Pad16)") (class "Default")
      (node (ref "U2") (pin "16") (pinfunction "CHAN15_16") (pintype "bidirectional"))
    )
    (net (code "135") (name "unconnected-(U3-CHAN13-Pad18)") (class "Default")
      (node (ref "U3") (pin "18") (pinfunction "CHAN13_18") (pintype "bidirectional"))
    )
    (net (code "136") (name "unconnected-(U3-CHAN14-Pad17)") (class "Default")
      (node (ref "U3") (pin "17") (pinfunction "CHAN14_17") (pintype "bidirectional"))
    )
    (net (code "137") (name "unconnected-(U3-CHAN15-Pad16)") (class "Default")
      (node (ref "U3") (pin "16") (pinfunction "CHAN15_16") (pintype "bidirectional"))
    )
  )
)
